# Adafruit_PiCowbell_Adalogger.net
KiCad netlist of a schematic drawn in EAGLE
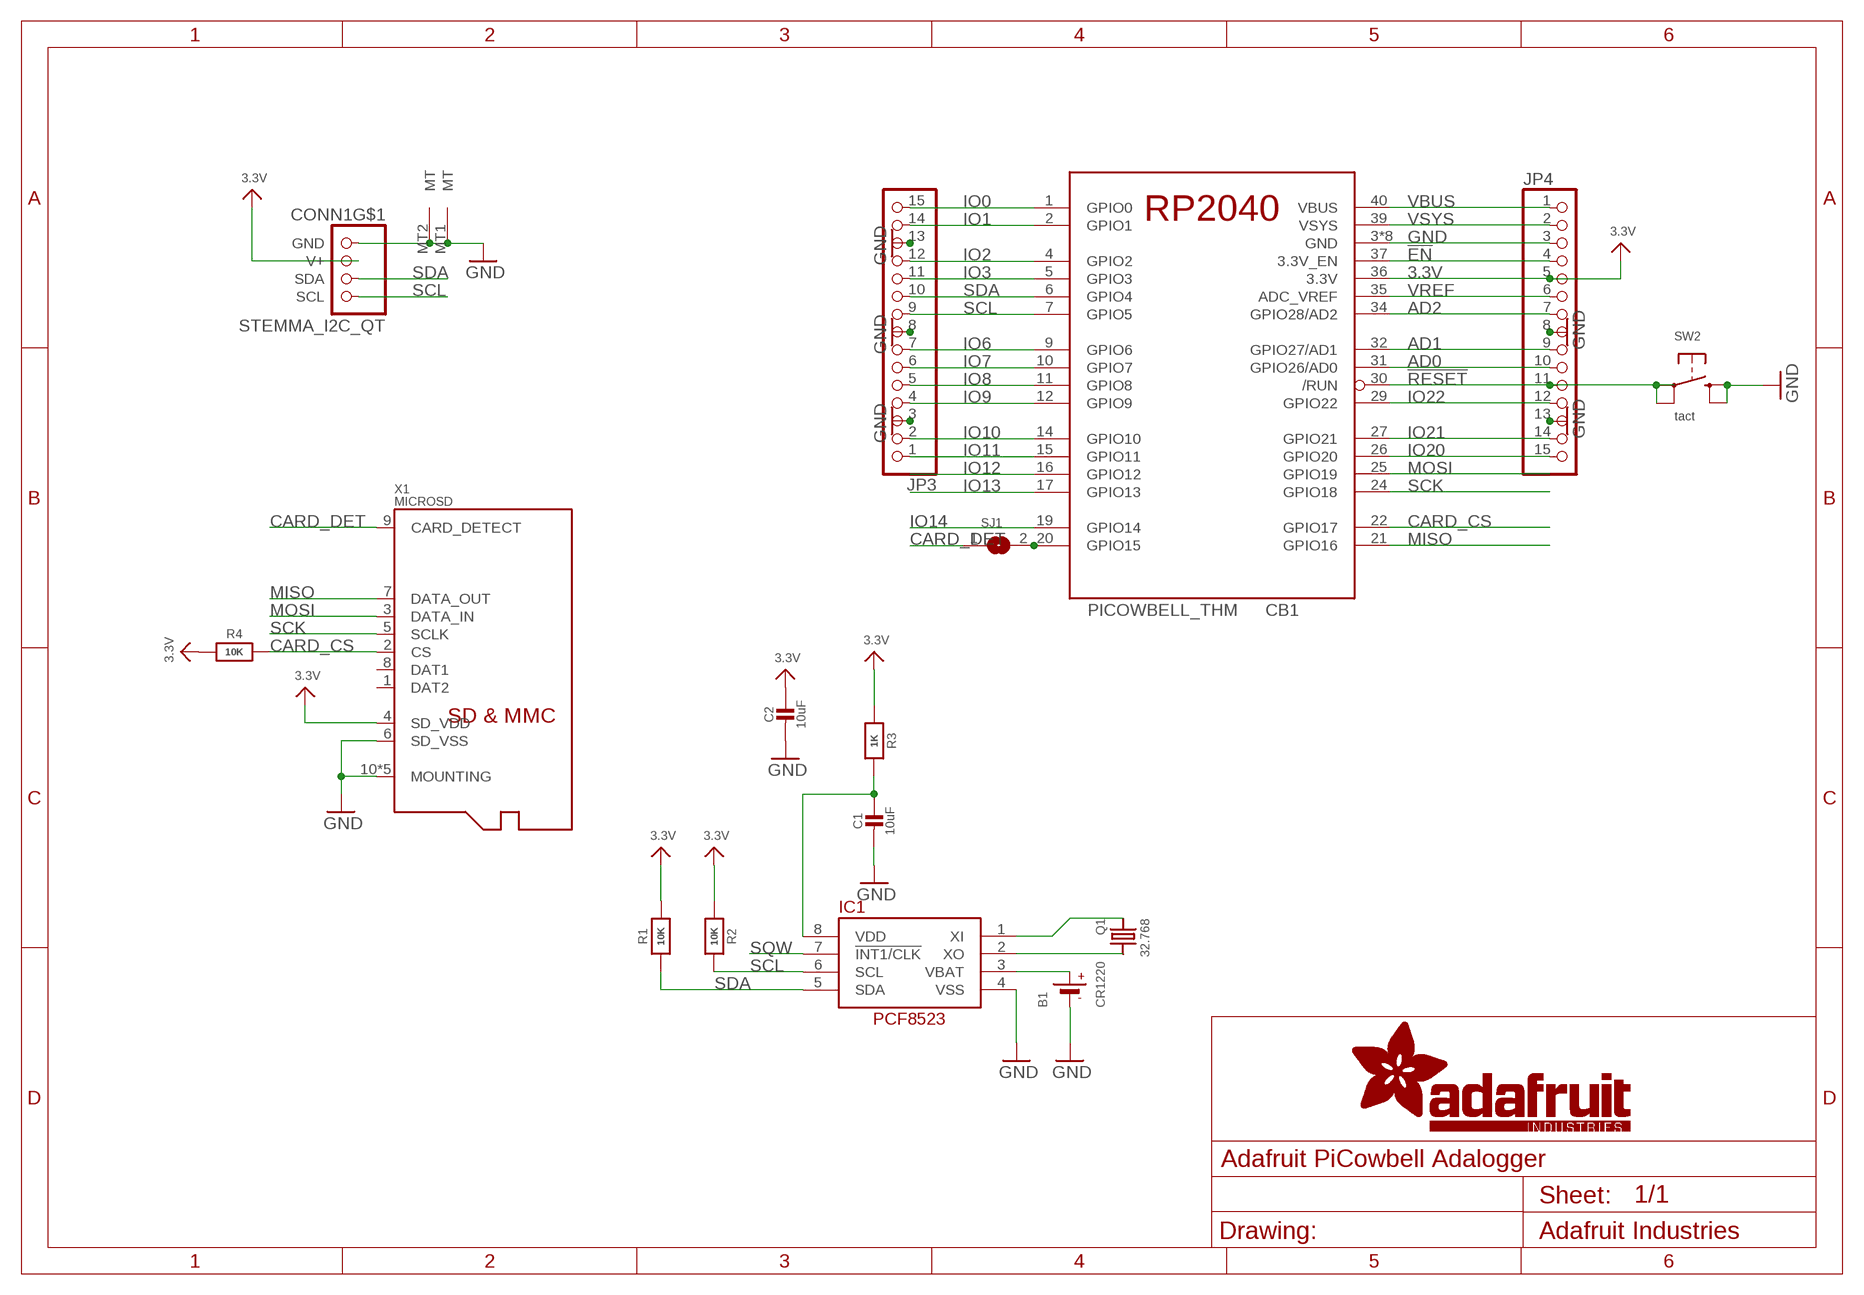
[diagram p0: schematic, sheet 1]

(export (version "E")
  (design (tool "Eeschema 10.0.6"))
  (components
    (comp (ref "B1")
      (value "CR1220")
      (footprint "eagle-import:CR1220-2")
      (libsource (lib "eagle-import") (part "BATTERYCR1220_2"))
    )
    (comp (ref "C1")
      (value "10uF")
      (footprint "eagle-import:0805-NO")
      (libsource (lib "eagle-import") (part "CAP_CERAMIC0805-NOOUTLINE"))
    )
    (comp (ref "C2")
      (value "10uF")
      (footprint "eagle-import:0805-NO")
      (libsource (lib "eagle-import") (part "CAP_CERAMIC0805-NOOUTLINE"))
    )
    (comp (ref "CB1")
      (value "PICOWBELL_THM")
      (footprint "eagle-import:PICOWBELL_THM")
      (libsource (lib "eagle-import") (part "PICOWBELL_THM"))
    )
    (comp (ref "CONN1")
      (value "STEMMA_I2C_QT")
      (footprint "eagle-import:JST_SH4")
      (libsource (lib "eagle-import") (part "STEMMA_I2C_QT"))
    )
    (comp (ref "IC1")
      (value "RTC_PCF8523/T")
      (footprint "eagle-import:SOIC8_150MIL")
      (libsource (lib "eagle-import") (part "RTC_PCF8523/T"))
    )
    (comp (ref "JP3")
      (value "HEADER-1X15")
      (footprint "eagle-import:1X15_ROUND_70")
      (libsource (lib "eagle-import") (part "HEADER-1X15"))
    )
    (comp (ref "JP4")
      (value "HEADER-1X15")
      (footprint "eagle-import:1X15_ROUND_70")
      (libsource (lib "eagle-import") (part "HEADER-1X15"))
    )
    (comp (ref "Q1")
      (value "32.768")
      (footprint "eagle-import:XTAL3215")
      (libsource (lib "eagle-import") (part "CRYSTAL_3215"))
    )
    (comp (ref "R1")
      (value "10K")
      (footprint "eagle-import:0603-NO")
      (libsource (lib "eagle-import") (part "RESISTOR_0603_NOOUT"))
    )
    (comp (ref "R2")
      (value "10K")
      (footprint "eagle-import:0603-NO")
      (libsource (lib "eagle-import") (part "RESISTOR_0603_NOOUT"))
    )
    (comp (ref "R3")
      (value "1K")
      (footprint "eagle-import:0603-NO")
      (libsource (lib "eagle-import") (part "RESISTOR_0603_NOOUT"))
    )
    (comp (ref "R4")
      (value "10K")
      (footprint "eagle-import:0603-NO")
      (libsource (lib "eagle-import") (part "RESISTOR_0603_NOOUT"))
    )
    (comp (ref "SJ1")
      (value "SOLDERJUMPER")
      (footprint "eagle-import:SOLDERJUMPER_ARROW_NOPASTE")
      (libsource (lib "eagle-import") (part "SOLDERJUMPER"))
    )
    (comp (ref "SW2")
      (value "tact")
      (footprint "eagle-import:BTN_RKB2_4.6X2.8")
      (libsource (lib "eagle-import") (part "SWITCH_TACT_SMT_RKB2"))
    )
    (comp (ref "X1")
      (value "MICROSD")
      (footprint "eagle-import:MOLEX_104031-0811")
      (libsource (lib "eagle-import") (part "MICROSD104031-0811"))
    )
  )
  (nets
    (net (code "1") (name "/AD0") (class "Default")
      (node (ref "CB1") (pin "31") (pinfunction "GPIO26/AD0_31") (pintype "bidirectional"))
      (node (ref "JP4") (pin "10") (pinfunction "10_10") (pintype "passive"))
    )
    (net (code "2") (name "/AD1") (class "Default")
      (node (ref "CB1") (pin "32") (pinfunction "GPIO27/AD1_32") (pintype "bidirectional"))
      (node (ref "JP4") (pin "9") (pinfunction "9_9") (pintype "passive"))
    )
    (net (code "3") (name "/AD2") (class "Default")
      (node (ref "CB1") (pin "34") (pinfunction "GPIO28/AD2_34") (pintype "bidirectional"))
      (node (ref "JP4") (pin "7") (pinfunction "7_7") (pintype "passive"))
    )
    (net (code "4") (name "/CARD_CS") (class "Default")
      (node (ref "CB1") (pin "22") (pinfunction "GPIO17_22") (pintype "bidirectional"))
      (node (ref "R4") (pin "2") (pinfunction "2_2") (pintype "passive"))
      (node (ref "X1") (pin "2") (pinfunction "CS_2") (pintype "input"))
    )
    (net (code "5") (name "/CARD_DET") (class "Default")
      (node (ref "SJ1") (pin "1") (pinfunction "1_1") (pintype "passive"))
      (node (ref "X1") (pin "9") (pinfunction "CARD_DETECT_9") (pintype "passive"))
    )
    (net (code "6") (name "/IO0") (class "Default")
      (node (ref "CB1") (pin "1") (pinfunction "GPIO0_1") (pintype "bidirectional"))
      (node (ref "JP3") (pin "15") (pinfunction "15_15") (pintype "passive"))
    )
    (net (code "7") (name "/IO1") (class "Default")
      (node (ref "CB1") (pin "2") (pinfunction "GPIO1_2") (pintype "bidirectional"))
      (node (ref "JP3") (pin "14") (pinfunction "14_14") (pintype "passive"))
    )
    (net (code "8") (name "/IO2") (class "Default")
      (node (ref "CB1") (pin "4") (pinfunction "GPIO2_4") (pintype "bidirectional"))
      (node (ref "JP3") (pin "12") (pinfunction "12_12") (pintype "passive"))
    )
    (net (code "9") (name "/IO3") (class "Default")
      (node (ref "CB1") (pin "5") (pinfunction "GPIO3_5") (pintype "bidirectional"))
      (node (ref "JP3") (pin "11") (pinfunction "11_11") (pintype "passive"))
    )
    (net (code "10") (name "/IO6") (class "Default")
      (node (ref "CB1") (pin "9") (pinfunction "GPIO6_9") (pintype "bidirectional"))
      (node (ref "JP3") (pin "7") (pinfunction "7_7") (pintype "passive"))
    )
    (net (code "11") (name "/IO7") (class "Default")
      (node (ref "CB1") (pin "10") (pinfunction "GPIO7_10") (pintype "bidirectional"))
      (node (ref "JP3") (pin "6") (pinfunction "6_6") (pintype "passive"))
    )
    (net (code "12") (name "/IO8") (class "Default")
      (node (ref "CB1") (pin "11") (pinfunction "GPIO8_11") (pintype "bidirectional"))
      (node (ref "JP3") (pin "5") (pinfunction "5_5") (pintype "passive"))
    )
    (net (code "13") (name "/IO9") (class "Default")
      (node (ref "CB1") (pin "12") (pinfunction "GPIO9_12") (pintype "bidirectional"))
      (node (ref "JP3") (pin "4") (pinfunction "4_4") (pintype "passive"))
    )
    (net (code "14") (name "/IO10") (class "Default")
      (node (ref "CB1") (pin "14") (pinfunction "GPIO10_14") (pintype "bidirectional"))
      (node (ref "JP3") (pin "2") (pinfunction "2_2") (pintype "passive"))
    )
    (net (code "15") (name "/IO11") (class "Default")
      (node (ref "CB1") (pin "15") (pinfunction "GPIO11_15") (pintype "bidirectional"))
      (node (ref "JP3") (pin "1") (pinfunction "1_1") (pintype "passive"))
    )
    (net (code "16") (name "/IO12") (class "Default")
      (node (ref "CB1") (pin "16") (pinfunction "GPIO12_16") (pintype "bidirectional"))
    )
    (net (code "17") (name "/IO13") (class "Default")
      (node (ref "CB1") (pin "17") (pinfunction "GPIO13_17") (pintype "bidirectional"))
    )
    (net (code "18") (name "/IO14") (class "Default")
      (node (ref "CB1") (pin "19") (pinfunction "GPIO14_19") (pintype "bidirectional"))
    )
    (net (code "19") (name "/IO20") (class "Default")
      (node (ref "CB1") (pin "26") (pinfunction "GPIO20_26") (pintype "bidirectional"))
      (node (ref "JP4") (pin "15") (pinfunction "15_15") (pintype "passive"))
    )
    (net (code "20") (name "/IO21") (class "Default")
      (node (ref "CB1") (pin "27") (pinfunction "GPIO21_27") (pintype "bidirectional"))
      (node (ref "JP4") (pin "14") (pinfunction "14_14") (pintype "passive"))
    )
    (net (code "21") (name "/IO22") (class "Default")
      (node (ref "CB1") (pin "29") (pinfunction "GPIO22_29") (pintype "bidirectional"))
      (node (ref "JP4") (pin "12") (pinfunction "12_12") (pintype "passive"))
    )
    (net (code "22") (name "/MISO") (class "Default")
      (node (ref "CB1") (pin "21") (pinfunction "GPIO16_21") (pintype "bidirectional"))
      (node (ref "X1") (pin "7") (pinfunction "DATA_OUT_7") (pintype "output"))
    )
    (net (code "23") (name "/MOSI") (class "Default")
      (node (ref "CB1") (pin "25") (pinfunction "GPIO19_25") (pintype "bidirectional"))
      (node (ref "X1") (pin "3") (pinfunction "DATA_IN_3") (pintype "input"))
    )
    (net (code "24") (name "/SCK") (class "Default")
      (node (ref "CB1") (pin "24") (pinfunction "GPIO18_24") (pintype "bidirectional"))
      (node (ref "X1") (pin "5") (pinfunction "SCLK_5") (pintype "input"))
    )
    (net (code "25") (name "/SCL") (class "Default")
      (node (ref "CB1") (pin "7") (pinfunction "GPIO5_7") (pintype "bidirectional"))
      (node (ref "CONN1") (pin "4") (pinfunction "SCL_4") (pintype "passive"))
      (node (ref "IC1") (pin "6") (pinfunction "SCL_6") (pintype "bidirectional"))
      (node (ref "JP3") (pin "9") (pinfunction "9_9") (pintype "passive"))
      (node (ref "R2") (pin "2") (pinfunction "2_2") (pintype "passive"))
    )
    (net (code "26") (name "/SDA") (class "Default")
      (node (ref "CB1") (pin "6") (pinfunction "GPIO4_6") (pintype "bidirectional"))
      (node (ref "CONN1") (pin "3") (pinfunction "SDA_3") (pintype "passive"))
      (node (ref "IC1") (pin "5") (pinfunction "SDA_5") (pintype "bidirectional"))
      (node (ref "JP3") (pin "10") (pinfunction "10_10") (pintype "passive"))
      (node (ref "R1") (pin "1") (pinfunction "1_1") (pintype "passive"))
    )
    (net (code "27") (name "/SQW") (class "Default")
      (node (ref "IC1") (pin "7") (pinfunction "~{INT1/CLK}_7") (pintype "output"))
    )
    (net (code "28") (name "/VBUS") (class "Default")
      (node (ref "CB1") (pin "40") (pinfunction "VBUS_40") (pintype "power_in"))
      (node (ref "JP4") (pin "1") (pinfunction "1_1") (pintype "passive"))
    )
    (net (code "29") (name "/VREF") (class "Default")
      (node (ref "CB1") (pin "35") (pinfunction "ADC_VREF_35") (pintype "passive"))
      (node (ref "JP4") (pin "6") (pinfunction "6_6") (pintype "passive"))
    )
    (net (code "30") (name "/VSYS") (class "Default")
      (node (ref "CB1") (pin "39") (pinfunction "VSYS_39") (pintype "power_in"))
      (node (ref "JP4") (pin "2") (pinfunction "2_2") (pintype "passive"))
    )
    (net (code "31") (name "/~{EN}") (class "Default")
      (node (ref "CB1") (pin "37") (pinfunction "3.3V_EN_37") (pintype "passive"))
      (node (ref "JP4") (pin "4") (pinfunction "4_4") (pintype "passive"))
    )
    (net (code "32") (name "/~{RESET}") (class "Default")
      (node (ref "CB1") (pin "30") (pinfunction "/RUN_30") (pintype "bidirectional"))
      (node (ref "JP4") (pin "11") (pinfunction "11_11") (pintype "passive"))
      (node (ref "SW2") (pin "A") (pinfunction "P_A") (pintype "passive"))
      (node (ref "SW2") (pin "A'") (pinfunction "P1_A'") (pintype "passive"))
    )
    (net (code "33") (name "3.3V") (class "Default")
      (node (ref "C2") (pin "1") (pinfunction "1_1") (pintype "passive"))
      (node (ref "CB1") (pin "36") (pinfunction "3.3V_36") (pintype "power_in"))
      (node (ref "CONN1") (pin "2") (pinfunction "V+_2") (pintype "passive"))
      (node (ref "JP4") (pin "5") (pinfunction "5_5") (pintype "passive"))
      (node (ref "R1") (pin "2") (pinfunction "2_2") (pintype "passive"))
      (node (ref "R2") (pin "1") (pinfunction "1_1") (pintype "passive"))
      (node (ref "R3") (pin "1") (pinfunction "1_1") (pintype "passive"))
      (node (ref "R4") (pin "1") (pinfunction "1_1") (pintype "passive"))
      (node (ref "X1") (pin "4") (pinfunction "SD_VDD_4") (pintype "power_in"))
    )
    (net (code "34") (name "GND") (class "Default")
      (node (ref "B1") (pin "-") (pinfunction "-_-") (pintype "passive"))
      (node (ref "C1") (pin "2") (pinfunction "2_2") (pintype "passive"))
      (node (ref "C2") (pin "2") (pinfunction "2_2") (pintype "passive"))
      (node (ref "CB1") (pin "13") (pinfunction "GND_13") (pintype "power_in"))
      (node (ref "CB1") (pin "18") (pinfunction "GND_18") (pintype "power_in"))
      (node (ref "CB1") (pin "23") (pinfunction "GND_23") (pintype "power_in"))
      (node (ref "CB1") (pin "28") (pinfunction "GND_28") (pintype "power_in"))
      (node (ref "CB1") (pin "3") (pinfunction "GND_3") (pintype "power_in"))
      (node (ref "CB1") (pin "33") (pinfunction "GND_33") (pintype "power_in"))
      (node (ref "CB1") (pin "38") (pinfunction "GND_38") (pintype "power_in"))
      (node (ref "CB1") (pin "8") (pinfunction "GND_8") (pintype "power_in"))
      (node (ref "CONN1") (pin "1") (pinfunction "GND_1") (pintype "passive"))
      (node (ref "CONN1") (pin "MT1") (pinfunction "MT_MT1") (pintype "bidirectional"))
      (node (ref "CONN1") (pin "MT2") (pinfunction "MT_MT2") (pintype "bidirectional"))
      (node (ref "IC1") (pin "4") (pinfunction "VSS_4") (pintype "power_in"))
      (node (ref "JP3") (pin "13") (pinfunction "13_13") (pintype "passive"))
      (node (ref "JP3") (pin "3") (pinfunction "3_3") (pintype "passive"))
      (node (ref "JP3") (pin "8") (pinfunction "8_8") (pintype "passive"))
      (node (ref "JP4") (pin "13") (pinfunction "13_13") (pintype "passive"))
      (node (ref "JP4") (pin "3") (pinfunction "3_3") (pintype "passive"))
      (node (ref "JP4") (pin "8") (pinfunction "8_8") (pintype "passive"))
      (node (ref "SW2") (pin "B") (pinfunction "S_B") (pintype "passive"))
      (node (ref "SW2") (pin "B'") (pinfunction "S1_B'") (pintype "passive"))
      (node (ref "X1") (pin "10") (pinfunction "MOUNTING_10") (pintype "passive"))
      (node (ref "X1") (pin "6") (pinfunction "SD_VSS_6") (pintype "power_in"))
      (node (ref "X1") (pin "G1") (pinfunction "MOUNTING_G1") (pintype "passive"))
      (node (ref "X1") (pin "G2") (pinfunction "MOUNTING_G2") (pintype "passive"))
      (node (ref "X1") (pin "G3") (pinfunction "MOUNTING_G3") (pintype "passive"))
      (node (ref "X1") (pin "G4") (pinfunction "MOUNTING_G4") (pintype "passive"))
    )
    (net (code "35") (name "Net-(CB1-GPIO15)") (class "Default")
      (node (ref "CB1") (pin "20") (pinfunction "GPIO15_20") (pintype "bidirectional"))
      (node (ref "SJ1") (pin "2") (pinfunction "2_2") (pintype "passive"))
    )
    (net (code "36") (name "Net-(IC1-VBAT)") (class "Default")
      (node (ref "B1") (pin "+") (pinfunction "+_+") (pintype "passive"))
      (node (ref "IC1") (pin "3") (pinfunction "VBAT_3") (pintype "power_in"))
    )
    (net (code "37") (name "Net-(IC1-VDD)") (class "Default")
      (node (ref "C1") (pin "1") (pinfunction "1_1") (pintype "passive"))
      (node (ref "IC1") (pin "8") (pinfunction "VDD_8") (pintype "power_in"))
      (node (ref "R3") (pin "2") (pinfunction "2_2") (pintype "passive"))
    )
    (net (code "38") (name "Net-(IC1-XI)") (class "Default")
      (node (ref "IC1") (pin "1") (pinfunction "XI_1") (pintype "input"))
      (node (ref "Q1") (pin "P$1") (pinfunction "1_P$1") (pintype "passive"))
    )
    (net (code "39") (name "Net-(IC1-XO)") (class "Default")
      (node (ref "IC1") (pin "2") (pinfunction "XO_2") (pintype "output"))
      (node (ref "Q1") (pin "P$2") (pinfunction "2_P$2") (pintype "passive"))
    )
    (net (code "40") (name "unconnected-(X1-DAT1-Pad8)") (class "Default")
      (node (ref "X1") (pin "8") (pinfunction "DAT1_8") (pintype "bidirectional"))
    )
    (net (code "41") (name "unconnected-(X1-DAT2-Pad1)") (class "Default")
      (node (ref "X1") (pin "1") (pinfunction "DAT2_1") (pintype "bidirectional"))
    )
  )
)
